# ESP32_Module.net
KiCad netlist of a schematic drawn in Altium Designer
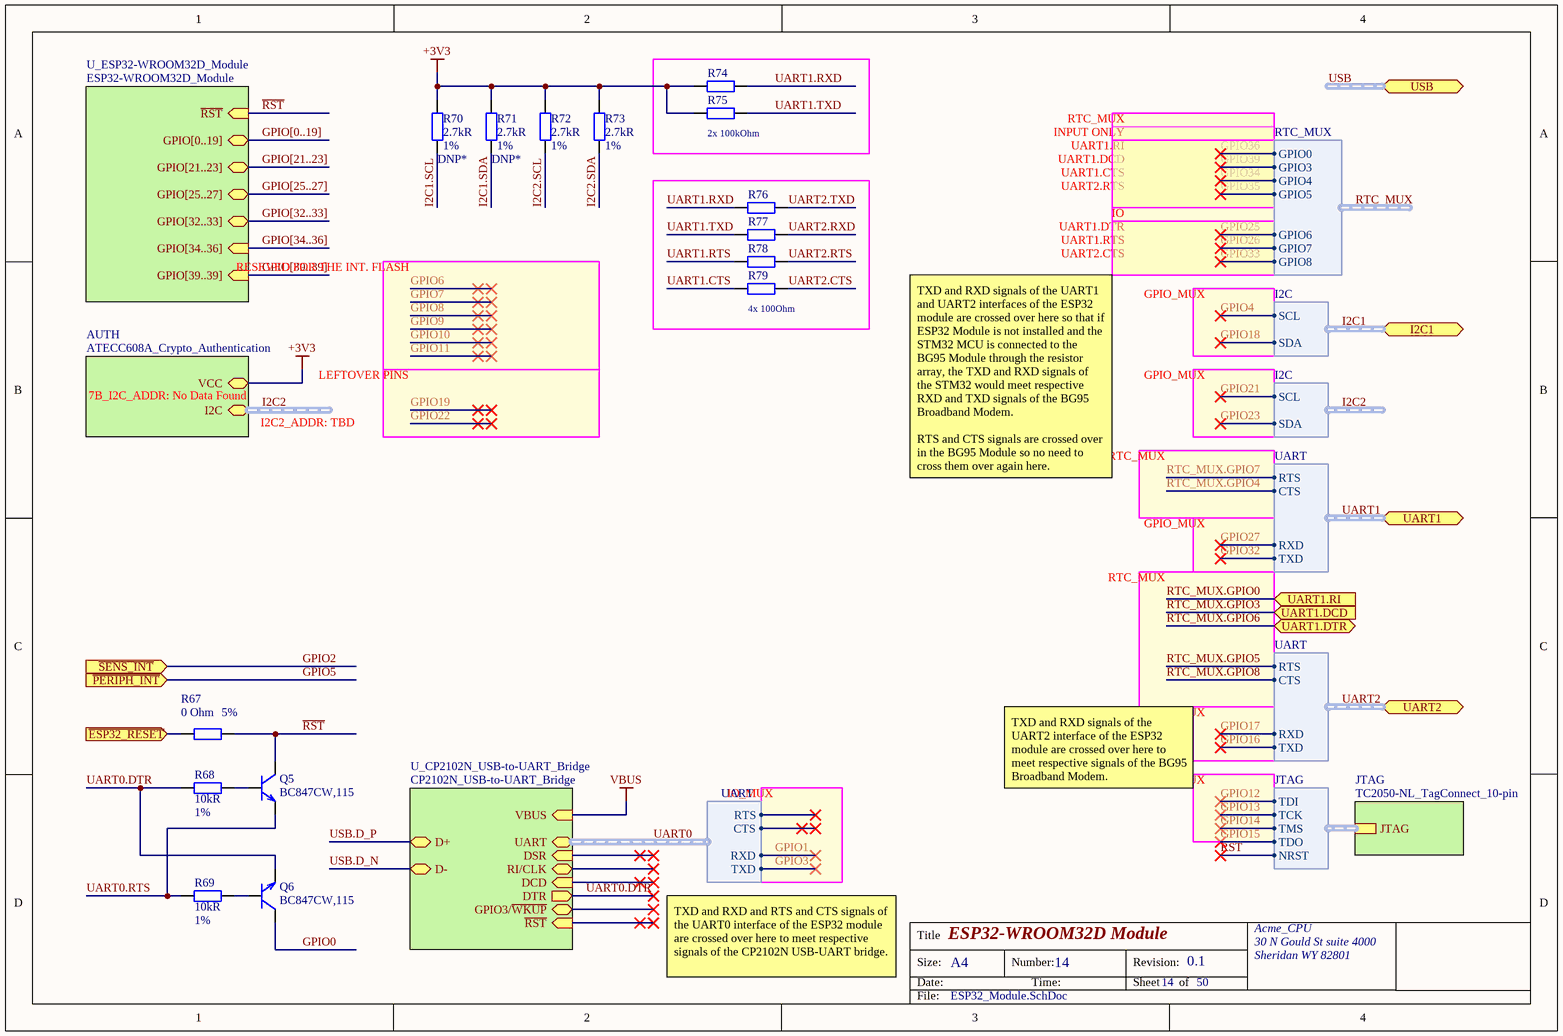
[diagram p0: ESP32_Module.SchDoc]

(export (version "E")
  (design (tool "Eeschema 10.0.6"))
  (components
    (comp (ref "Q5")
      (value "BC847CW,115")
      (footprint "SOT-323")
      (description "Bipolar (BJT) Transistor NPN 45V 100mA 100MHz 200mW Surface Mount SOT-323-3")
      (fields (field (name "MANUFACTURER") "Nexperia"))
      (libsource (lib "bipolar-junction_transistors") (part "TRANS BC847CW,115 NPN 45V 0.1A SOT323"))
    )
    (comp (ref "Q6")
      (value "BC847CW,115")
      (footprint "SOT-323")
      (description "Bipolar (BJT) Transistor NPN 45V 100mA 100MHz 200mW Surface Mount SOT-323-3")
      (fields (field (name "MANUFACTURER") "Nexperia"))
      (libsource (lib "bipolar-junction_transistors") (part "TRANS BC847CW,115 NPN 45V 0.1A SOT323"))
    )
    (comp (ref "R67")
      (value "RES SMD 0 OHM JUMPER 1/16W 0402")
      (footprint "R0402")
      (description "0 Ohms Jumper 0.063W, 1/16W Chip Resistor 0402 (1005 Metric) Moisture Resistant Thick Film")
      (fields
        (field (name "MANUFACTURER") "Yageo")
        (field (name "MANUFACTURER PART NUMBER") "RC0402JR-070RL")
        (field (name "TOLERANCE") "5%")
        (field (name "RESISTANCE") "0 Ohm")
      )
      (libsource (lib "resistors_smd") (part "RES SMD 0 OHM JUMPER 1/16W 0402"))
    )
    (comp (ref "R68")
      (value "RES SMD 10K OHM 1% 1/16W 0402")
      (footprint "R0402")
      (description "10 kOhms ±1% 0.063W, 1/16W Chip Resistor 0402 (1005 Metric) Moisture Resistant Thick Film")
      (fields
        (field (name "MANUFACTURER PART NUMBER") "RC0402FR-0710KP")
        (field (name "MANUFACTURER") "Yageo")
        (field (name "RESISTANCE") "10kR")
        (field (name "TOLERANCE") "1%")
      )
      (libsource (lib "resistors_smd") (part "RES SMD 10K OHM 1% 1/16W 0402"))
    )
    (comp (ref "R69")
      (value "RES SMD 10K OHM 1% 1/16W 0402")
      (footprint "R0402")
      (description "10 kOhms ±1% 0.063W, 1/16W Chip Resistor 0402 (1005 Metric) Moisture Resistant Thick Film")
      (fields
        (field (name "MANUFACTURER PART NUMBER") "RC0402FR-0710KP")
        (field (name "MANUFACTURER") "Yageo")
        (field (name "RESISTANCE") "10kR")
        (field (name "TOLERANCE") "1%")
      )
      (libsource (lib "resistors_smd") (part "RES SMD 10K OHM 1% 1/16W 0402"))
    )
    (comp (ref "R70")
      (value "DNP*")
      (footprint "R0402")
      (description "2.7 kOhms ±1% 0.063W, 1/16W Chip Resistor 0402 (1005 Metric) Moisture Resistant Thick Film")
      (fields
        (field (name "MANUFACTURER PART NUMBER") "RC0402FR-072K7L")
        (field (name "MANUFACTURER") "Yageo")
        (field (name "RESISTANCE") "2.7kR")
        (field (name "TOLERANCE") "1%")
      )
      (libsource (lib "resistors_smd") (part "RES SMD 2.7K OHM 1% 1/16W 0402"))
    )
    (comp (ref "R71")
      (value "DNP*")
      (footprint "R0402")
      (description "2.7 kOhms ±1% 0.063W, 1/16W Chip Resistor 0402 (1005 Metric) Moisture Resistant Thick Film")
      (fields
        (field (name "MANUFACTURER PART NUMBER") "RC0402FR-072K7L")
        (field (name "MANUFACTURER") "Yageo")
        (field (name "RESISTANCE") "2.7kR")
        (field (name "TOLERANCE") "1%")
      )
      (libsource (lib "resistors_smd") (part "RES SMD 2.7K OHM 1% 1/16W 0402"))
    )
    (comp (ref "R72")
      (value "RES SMD 2.7K OHM 1% 1/16W 0402")
      (footprint "R0402")
      (description "2.7 kOhms ±1% 0.063W, 1/16W Chip Resistor 0402 (1005 Metric) Moisture Resistant Thick Film")
      (fields
        (field (name "MANUFACTURER PART NUMBER") "RC0402FR-072K7L")
        (field (name "MANUFACTURER") "Yageo")
        (field (name "RESISTANCE") "2.7kR")
        (field (name "TOLERANCE") "1%")
      )
      (libsource (lib "resistors_smd") (part "RES SMD 2.7K OHM 1% 1/16W 0402"))
    )
    (comp (ref "R73")
      (value "RES SMD 2.7K OHM 1% 1/16W 0402")
      (footprint "R0402")
      (description "2.7 kOhms ±1% 0.063W, 1/16W Chip Resistor 0402 (1005 Metric) Moisture Resistant Thick Film")
      (fields
        (field (name "MANUFACTURER PART NUMBER") "RC0402FR-072K7L")
        (field (name "MANUFACTURER") "Yageo")
        (field (name "RESISTANCE") "2.7kR")
        (field (name "TOLERANCE") "1%")
      )
      (libsource (lib "resistors_smd") (part "RES SMD 2.7K OHM 1% 1/16W 0402"))
    )
    (comp (ref "R74")
      (value "RES SMD 100K OHM 1% 1/16W 0402")
      (footprint "R0402")
      (description "100 kOhms ±1% 0.063W, 1/16W Chip Resistor 0402 (1005 Metric) Moisture Resistant Thick Film")
      (fields
        (field (name "MANUFACTURER") "Yageo")
        (field (name "MANUFACTURER PART NUMBER") "RC0402FR-07100KL")
      )
      (libsource (lib "resistors_smd") (part "RES SMD 100K OHM 1% 1/16W 0402"))
    )
    (comp (ref "R75")
      (value "RES SMD 100K OHM 1% 1/16W 0402")
      (footprint "R0402")
      (description "100 kOhms ±1% 0.063W, 1/16W Chip Resistor 0402 (1005 Metric) Moisture Resistant Thick Film")
      (fields
        (field (name "MANUFACTURER") "Yageo")
        (field (name "MANUFACTURER PART NUMBER") "RC0402FR-07100KL")
      )
      (libsource (lib "resistors_smd") (part "RES SMD 100K OHM 1% 1/16W 0402"))
    )
    (comp (ref "R76")
      (value "RES SMD 100 OHM 1% 1/16W 0402")
      (footprint "R0402")
      (description "100 Ohms ±1% 0.063W, 1/16W Chip Resistor 0402 (1005 Metric) Moisture Resistant Thick Film")
      (fields
        (field (name "MANUFACTURER") "Yageo")
        (field (name "MANUFACTURER PART NUMBER") "RC0402FR-07100RL")
      )
      (libsource (lib "resistors_smd") (part "RES SMD 100 OHM 1% 1/16W 0402"))
    )
    (comp (ref "R77")
      (value "RES SMD 100 OHM 1% 1/16W 0402")
      (footprint "R0402")
      (description "100 Ohms ±1% 0.063W, 1/16W Chip Resistor 0402 (1005 Metric) Moisture Resistant Thick Film")
      (fields
        (field (name "MANUFACTURER") "Yageo")
        (field (name "MANUFACTURER PART NUMBER") "RC0402FR-07100RL")
      )
      (libsource (lib "resistors_smd") (part "RES SMD 100 OHM 1% 1/16W 0402"))
    )
    (comp (ref "R78")
      (value "RES SMD 100 OHM 1% 1/16W 0402")
      (footprint "R0402")
      (description "100 Ohms ±1% 0.063W, 1/16W Chip Resistor 0402 (1005 Metric) Moisture Resistant Thick Film")
      (fields
        (field (name "MANUFACTURER") "Yageo")
        (field (name "MANUFACTURER PART NUMBER") "RC0402FR-07100RL")
      )
      (libsource (lib "resistors_smd") (part "RES SMD 100 OHM 1% 1/16W 0402"))
    )
    (comp (ref "R79")
      (value "RES SMD 100 OHM 1% 1/16W 0402")
      (footprint "R0402")
      (description "100 Ohms ±1% 0.063W, 1/16W Chip Resistor 0402 (1005 Metric) Moisture Resistant Thick Film")
      (fields
        (field (name "MANUFACTURER") "Yageo")
        (field (name "MANUFACTURER PART NUMBER") "RC0402FR-07100RL")
      )
      (libsource (lib "resistors_smd") (part "RES SMD 100 OHM 1% 1/16W 0402"))
    )
  )
  (nets
    (net (code "11") (name "+3V3") (class "Default")
      (node (ref "R70") (pin "2") (pinfunction "2_2") (pintype "passive"))
      (node (ref "R71") (pin "2") (pinfunction "2_2") (pintype "passive"))
      (node (ref "R72") (pin "2") (pinfunction "2_2") (pintype "passive"))
      (node (ref "R73") (pin "2") (pinfunction "2_2") (pintype "passive"))
      (node (ref "R74") (pin "1") (pinfunction "1_1") (pintype "passive"))
      (node (ref "R75") (pin "1") (pinfunction "1_1") (pintype "passive"))
    )
    (net (code "14") (name "/ESP32_RESET") (class "Default")
      (node (ref "R67") (pin "1") (pinfunction "1_1") (pintype "passive"))
    )
    (net (code "15") (name "/GPIO0") (class "Default")
      (node (ref "Q6") (pin "3") (pinfunction "C_3") (pintype "passive"))
    )
    (net (code "53") (name "/I2C1.SCL") (class "Default")
      (node (ref "R70") (pin "1") (pinfunction "1_1") (pintype "passive"))
    )
    (net (code "54") (name "/I2C1.SDA") (class "Default")
      (node (ref "R71") (pin "1") (pinfunction "1_1") (pintype "passive"))
    )
    (net (code "56") (name "/I2C2.SCL") (class "Default")
      (node (ref "R72") (pin "1") (pinfunction "1_1") (pintype "passive"))
    )
    (net (code "57") (name "/I2C2.SDA") (class "Default")
      (node (ref "R73") (pin "1") (pinfunction "1_1") (pintype "passive"))
    )
    (net (code "60") (name "/RST") (class "Default")
      (node (ref "Q5") (pin "3") (pinfunction "C_3") (pintype "passive"))
      (node (ref "R67") (pin "2") (pinfunction "2_2") (pintype "passive"))
    )
    (net (code "70") (name "/UART0.DTR") (class "Default")
      (node (ref "Q6") (pin "2") (pinfunction "E_2") (pintype "passive"))
      (node (ref "R68") (pin "1") (pinfunction "1_1") (pintype "passive"))
    )
    (net (code "71") (name "/UART0.RTS") (class "Default")
      (node (ref "Q5") (pin "2") (pinfunction "E_2") (pintype "passive"))
      (node (ref "R69") (pin "1") (pinfunction "1_1") (pintype "passive"))
    )
    (net (code "73") (name "/UART1.CTS") (class "Default")
      (node (ref "R79") (pin "2") (pinfunction "2_2") (pintype "passive"))
    )
    (net (code "74") (name "/UART1.RTS") (class "Default")
      (node (ref "R78") (pin "2") (pinfunction "2_2") (pintype "passive"))
    )
    (net (code "75") (name "/UART1.RXD") (class "Default")
      (node (ref "R74") (pin "2") (pinfunction "2_2") (pintype "passive"))
      (node (ref "R76") (pin "2") (pinfunction "2_2") (pintype "passive"))
    )
    (net (code "76") (name "/UART1.TXD") (class "Default")
      (node (ref "R75") (pin "2") (pinfunction "2_2") (pintype "passive"))
      (node (ref "R77") (pin "2") (pinfunction "2_2") (pintype "passive"))
    )
    (net (code "78") (name "/UART2.CTS") (class "Default")
      (node (ref "R79") (pin "1") (pinfunction "1_1") (pintype "passive"))
    )
    (net (code "79") (name "/UART2.RTS") (class "Default")
      (node (ref "R78") (pin "1") (pinfunction "1_1") (pintype "passive"))
    )
    (net (code "80") (name "/UART2.RXD") (class "Default")
      (node (ref "R77") (pin "1") (pinfunction "1_1") (pintype "passive"))
    )
    (net (code "81") (name "/UART2.TXD") (class "Default")
      (node (ref "R76") (pin "1") (pinfunction "1_1") (pintype "passive"))
    )
    (net (code "89") (name "Net-(Q5-B)") (class "Default")
      (node (ref "Q5") (pin "1") (pinfunction "B_1") (pintype "passive"))
      (node (ref "R68") (pin "2") (pinfunction "2_2") (pintype "passive"))
    )
    (net (code "90") (name "Net-(Q6-B)") (class "Default")
      (node (ref "Q6") (pin "1") (pinfunction "B_1") (pintype "passive"))
      (node (ref "R69") (pin "2") (pinfunction "2_2") (pintype "passive"))
    )
  )
)
